# pcbgrado.net
KiCad netlist of a schematic drawn in Altium Designer
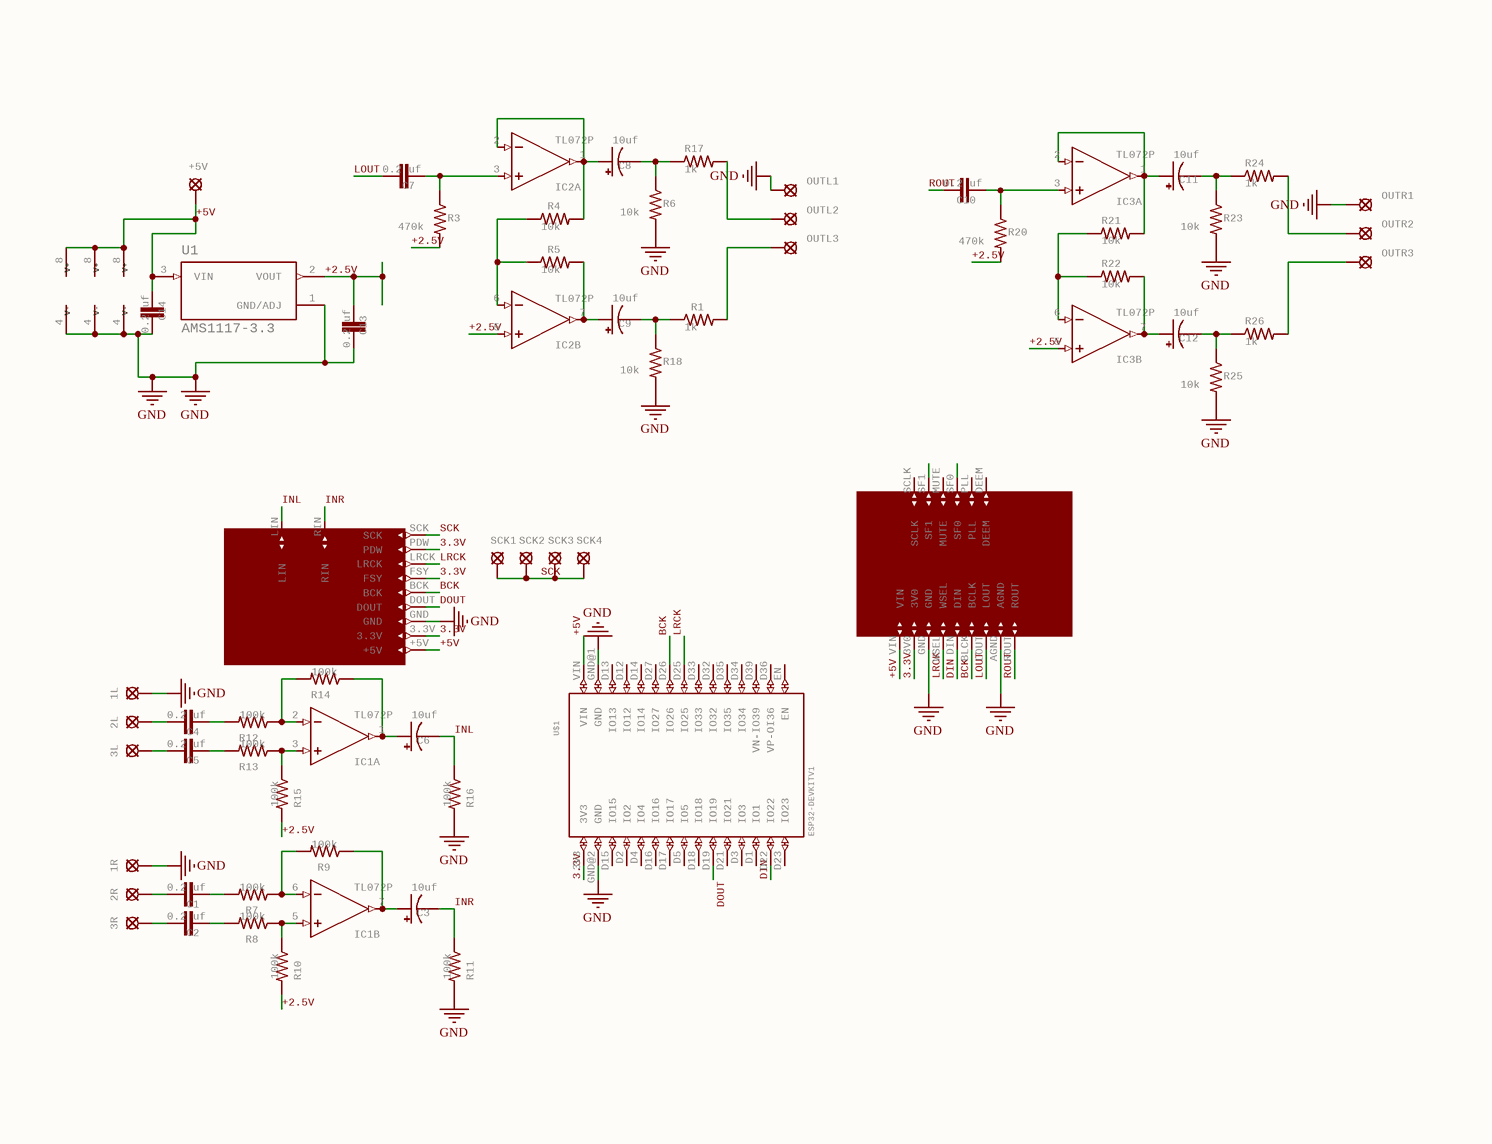
[diagram p0: pcbgrado.SchDoc]

(export (version "E")
  (design (tool "Eeschema 10.0.6"))
  (components
    (comp (ref "+5V")
      (value "LSP10")
      (footprint "LSP10")
      (description "SOLDER PAD    drill 1.0 mm, distributor Buerklin, 12H555")
      (fields (field (name "LIBRARYNAME") "solpad"))
      (libsource (lib "solpad") (part "LSP10"))
    )
    (comp (ref "1L")
      (value "LSP10")
      (footprint "LSP10")
      (description "SOLDER PAD    drill 1.0 mm, distributor Buerklin, 12H555")
      (fields (field (name "LIBRARYNAME") "solpad"))
      (libsource (lib "solpad") (part "LSP10"))
    )
    (comp (ref "1R")
      (value "LSP10")
      (footprint "LSP10")
      (description "SOLDER PAD    drill 1.0 mm, distributor Buerklin, 12H555")
      (fields (field (name "LIBRARYNAME") "solpad"))
      (libsource (lib "solpad") (part "LSP10"))
    )
    (comp (ref "2L")
      (value "LSP10")
      (footprint "LSP10")
      (description "SOLDER PAD    drill 1.0 mm, distributor Buerklin, 12H555")
      (fields (field (name "LIBRARYNAME") "solpad"))
      (libsource (lib "solpad") (part "LSP10"))
    )
    (comp (ref "2R")
      (value "LSP10")
      (footprint "LSP10")
      (description "SOLDER PAD    drill 1.0 mm, distributor Buerklin, 12H555")
      (fields (field (name "LIBRARYNAME") "solpad"))
      (libsource (lib "solpad") (part "LSP10"))
    )
    (comp (ref "3L")
      (value "LSP10")
      (footprint "LSP10")
      (description "SOLDER PAD    drill 1.0 mm, distributor Buerklin, 12H555")
      (fields (field (name "LIBRARYNAME") "solpad"))
      (libsource (lib "solpad") (part "LSP10"))
    )
    (comp (ref "3R")
      (value "LSP10")
      (footprint "LSP10")
      (description "SOLDER PAD    drill 1.0 mm, distributor Buerklin, 12H555")
      (fields (field (name "LIBRARYNAME") "solpad"))
      (libsource (lib "solpad") (part "LSP10"))
    )
    (comp (ref "C1")
      (value "C-EU025-025X050")
      (footprint "C025-025X050")
      (description "CAPACITOR, European symbol")
      (fields (field (name "POPULARITY") "0.2 uf"))
      (libsource (lib "rcl") (part "C-EU025-025X050"))
    )
    (comp (ref "C2")
      (value "C-EU025-025X050")
      (footprint "C025-025X050")
      (description "CAPACITOR, European symbol")
      (fields (field (name "POPULARITY") "0.2 uf"))
      (libsource (lib "rcl") (part "C-EU025-025X050"))
    )
    (comp (ref "C3")
      (value "CPOL-USE1.8-4")
      (footprint "E1,8-4")
      (description "POLARIZED CAPACITOR, American symbol")
      (fields (field (name "POPULARITY") "10uf"))
      (libsource (lib "rcl") (part "CPOL-USE1.8-4"))
    )
    (comp (ref "C4")
      (value "C-EU025-025X050")
      (footprint "C025-025X050")
      (description "CAPACITOR, European symbol")
      (fields (field (name "POPULARITY") "0.2 uf"))
      (libsource (lib "rcl") (part "C-EU025-025X050"))
    )
    (comp (ref "C5")
      (value "C-EU025-025X050")
      (footprint "C025-025X050")
      (description "CAPACITOR, European symbol")
      (fields (field (name "POPULARITY") "0.2 uf"))
      (libsource (lib "rcl") (part "C-EU025-025X050"))
    )
    (comp (ref "C6")
      (value "CPOL-USE1.8-4")
      (footprint "E1,8-4")
      (description "POLARIZED CAPACITOR, American symbol")
      (fields (field (name "POPULARITY") "10uf"))
      (libsource (lib "rcl") (part "CPOL-USE1.8-4"))
    )
    (comp (ref "C7")
      (value "C-EU025-030X050")
      (footprint "C025-030X050")
      (description "CAPACITOR, European symbol")
      (fields (field (name "POPULARITY") "0.2 uf"))
      (libsource (lib "rcl") (part "C-EU025-030X050"))
    )
    (comp (ref "C8")
      (value "CPOL-USE1.8-4")
      (footprint "E1,8-4")
      (description "POLARIZED CAPACITOR, American symbol")
      (fields (field (name "POPULARITY") "10uf"))
      (libsource (lib "rcl") (part "CPOL-USE1.8-4"))
    )
    (comp (ref "C9")
      (value "CPOL-USE1.8-4")
      (footprint "E1,8-4")
      (description "POLARIZED CAPACITOR, American symbol")
      (fields (field (name "POPULARITY") "10uf"))
      (libsource (lib "rcl") (part "CPOL-USE1.8-4"))
    )
    (comp (ref "C10")
      (value "C-EU025-030X050")
      (footprint "C025-030X050")
      (description "CAPACITOR, European symbol")
      (fields (field (name "POPULARITY") "0.2 uf"))
      (libsource (lib "rcl") (part "C-EU025-030X050"))
    )
    (comp (ref "C11")
      (value "CPOL-USE1.8-4")
      (footprint "E1,8-4")
      (description "POLARIZED CAPACITOR, American symbol")
      (fields (field (name "POPULARITY") "10uf"))
      (libsource (lib "rcl") (part "CPOL-USE1.8-4"))
    )
    (comp (ref "C12")
      (value "CPOL-USE1.8-4")
      (footprint "E1,8-4")
      (description "POLARIZED CAPACITOR, American symbol")
      (fields (field (name "POPULARITY") "10uf"))
      (libsource (lib "rcl") (part "CPOL-USE1.8-4"))
    )
    (comp (ref "C13")
      (value "C-EU025-025X050")
      (footprint "C025-025X050")
      (description "CAPACITOR, European symbol")
      (fields (field (name "POPULARITY") "0.2 uf"))
      (libsource (lib "") (part "C-EU025-025X050_1"))
    )
    (comp (ref "C14")
      (value "C-EU025-025X050")
      (footprint "C025-025X050")
      (description "CAPACITOR, European symbol")
      (fields (field (name "POPULARITY") "0.2 uf"))
      (libsource (lib "") (part "C-EU025-025X050_1"))
    )
    (comp (ref "IC1")
      (value "TL072P")
      (footprint "DIL08")
      (description "OP AMP")
      (fields (field (name "V+") "V+") (field (name "V-") "V-"))
      (libsource (lib "linear") (part "TL072P"))
    )
    (comp (ref "IC2")
      (value "TL072P")
      (footprint "DIL08")
      (description "OP AMP")
      (fields (field (name "V+") "V+") (field (name "V-") "V-"))
      (libsource (lib "linear") (part "TL072P"))
    )
    (comp (ref "IC3")
      (value "TL072P")
      (footprint "DIL08")
      (description "OP AMP")
      (fields (field (name "V+") "V+") (field (name "V-") "V-"))
      (libsource (lib "linear") (part "TL072P"))
    )
    (comp (ref "OUTL1")
      (value "LSP10")
      (footprint "LSP10")
      (description "SOLDER PAD    drill 1.0 mm, distributor Buerklin, 12H555")
      (fields (field (name "LIBRARYNAME") "solpad"))
      (libsource (lib "solpad") (part "LSP10"))
    )
    (comp (ref "OUTL2")
      (value "LSP10")
      (footprint "LSP10")
      (description "SOLDER PAD    drill 1.0 mm, distributor Buerklin, 12H555")
      (fields (field (name "LIBRARYNAME") "solpad"))
      (libsource (lib "solpad") (part "LSP10"))
    )
    (comp (ref "OUTL3")
      (value "LSP10")
      (footprint "LSP10")
      (description "SOLDER PAD    drill 1.0 mm, distributor Buerklin, 12H555")
      (fields (field (name "LIBRARYNAME") "solpad"))
      (libsource (lib "solpad") (part "LSP10"))
    )
    (comp (ref "OUTR1")
      (value "LSP10")
      (footprint "LSP10")
      (description "SOLDER PAD    drill 1.0 mm, distributor Buerklin, 12H555")
      (fields (field (name "LIBRARYNAME") "solpad"))
      (libsource (lib "solpad") (part "LSP10"))
    )
    (comp (ref "OUTR2")
      (value "LSP10")
      (footprint "LSP10")
      (description "SOLDER PAD    drill 1.0 mm, distributor Buerklin, 12H555")
      (fields (field (name "LIBRARYNAME") "solpad"))
      (libsource (lib "solpad") (part "LSP10"))
    )
    (comp (ref "OUTR3")
      (value "LSP10")
      (footprint "LSP10")
      (description "SOLDER PAD    drill 1.0 mm, distributor Buerklin, 12H555")
      (fields (field (name "LIBRARYNAME") "solpad"))
      (libsource (lib "solpad") (part "LSP10"))
    )
    (comp (ref "R1")
      (value "R-US_0204/7")
      (footprint "0204/7")
      (description "RESISTOR, American symbol")
      (fields (field (name "POPULARITY") "1k"))
      (libsource (lib "rcl") (part "R-US_0204/7"))
    )
    (comp (ref "R3")
      (value "R-US_0204/7")
      (footprint "0204/7")
      (description "RESISTOR, American symbol")
      (fields (field (name "POPULARITY") "470k"))
      (libsource (lib "rcl") (part "R-US_0204/7"))
    )
    (comp (ref "R4")
      (value "R-US_0204/7")
      (footprint "0204/7")
      (description "RESISTOR, American symbol")
      (fields (field (name "POPULARITY") "10k"))
      (libsource (lib "rcl") (part "R-US_0204/7"))
    )
    (comp (ref "R5")
      (value "R-US_0204/7")
      (footprint "0204/7")
      (description "RESISTOR, American symbol")
      (fields (field (name "POPULARITY") "10k"))
      (libsource (lib "rcl") (part "R-US_0204/7"))
    )
    (comp (ref "R6")
      (value "R-US_0204/7")
      (footprint "0204/7")
      (description "RESISTOR, American symbol")
      (fields (field (name "POPULARITY") "10k"))
      (libsource (lib "rcl") (part "R-US_0204/7"))
    )
    (comp (ref "R7")
      (value "R-US_0204/7")
      (footprint "0204/7")
      (description "RESISTOR, American symbol")
      (fields (field (name "POPULARITY") "100k"))
      (libsource (lib "rcl") (part "R-US_0204/7"))
    )
    (comp (ref "R8")
      (value "R-US_0204/7")
      (footprint "0204/7")
      (description "RESISTOR, American symbol")
      (fields (field (name "POPULARITY") "100k"))
      (libsource (lib "rcl") (part "R-US_0204/7"))
    )
    (comp (ref "R9")
      (value "R-US_0204/7")
      (footprint "0204/7")
      (description "RESISTOR, American symbol")
      (fields (field (name "POPULARITY") "100k"))
      (libsource (lib "rcl") (part "R-US_0204/7"))
    )
    (comp (ref "R10")
      (value "R-US_0204/7")
      (footprint "0204/7")
      (description "RESISTOR, American symbol")
      (fields (field (name "POPULARITY") "100k"))
      (libsource (lib "rcl") (part "R-US_0204/7"))
    )
    (comp (ref "R11")
      (value "R-US_0204/7")
      (footprint "0204/7")
      (description "RESISTOR, American symbol")
      (fields (field (name "POPULARITY") "100k"))
      (libsource (lib "rcl") (part "R-US_0204/7"))
    )
    (comp (ref "R12")
      (value "R-US_0204/7")
      (footprint "0204/7")
      (description "RESISTOR, American symbol")
      (fields (field (name "POPULARITY") "100k"))
      (libsource (lib "rcl") (part "R-US_0204/7"))
    )
    (comp (ref "R13")
      (value "R-US_0204/7")
      (footprint "0204/7")
      (description "RESISTOR, American symbol")
      (fields (field (name "POPULARITY") "100k"))
      (libsource (lib "rcl") (part "R-US_0204/7"))
    )
    (comp (ref "R14")
      (value "R-US_0204/7")
      (footprint "0204/7")
      (description "RESISTOR, American symbol")
      (fields (field (name "POPULARITY") "100k"))
      (libsource (lib "rcl") (part "R-US_0204/7"))
    )
    (comp (ref "R15")
      (value "R-US_0204/7")
      (footprint "0204/7")
      (description "RESISTOR, American symbol")
      (fields (field (name "POPULARITY") "100k"))
      (libsource (lib "rcl") (part "R-US_0204/7"))
    )
    (comp (ref "R16")
      (value "R-US_0204/7")
      (footprint "0204/7")
      (description "RESISTOR, American symbol")
      (fields (field (name "POPULARITY") "100k"))
      (libsource (lib "rcl") (part "R-US_0204/7"))
    )
    (comp (ref "R17")
      (value "R-US_0204/7")
      (footprint "0204/7")
      (description "RESISTOR, American symbol")
      (fields (field (name "POPULARITY") "1k"))
      (libsource (lib "rcl") (part "R-US_0204/7"))
    )
    (comp (ref "R18")
      (value "R-US_0204/7")
      (footprint "0204/7")
      (description "RESISTOR, American symbol")
      (fields (field (name "POPULARITY") "10k"))
      (libsource (lib "rcl") (part "R-US_0204/7"))
    )
    (comp (ref "R20")
      (value "R-US_0204/7")
      (footprint "0204/7")
      (description "RESISTOR, American symbol")
      (fields (field (name "POPULARITY") "470k"))
      (libsource (lib "rcl") (part "R-US_0204/7"))
    )
    (comp (ref "R21")
      (value "R-US_0204/7")
      (footprint "0204/7")
      (description "RESISTOR, American symbol")
      (fields (field (name "POPULARITY") "10k"))
      (libsource (lib "rcl") (part "R-US_0204/7"))
    )
    (comp (ref "R22")
      (value "R-US_0204/7")
      (footprint "0204/7")
      (description "RESISTOR, American symbol")
      (fields (field (name "POPULARITY") "10k"))
      (libsource (lib "rcl") (part "R-US_0204/7"))
    )
    (comp (ref "R23")
      (value "R-US_0204/7")
      (footprint "0204/7")
      (description "RESISTOR, American symbol")
      (fields (field (name "POPULARITY") "10k"))
      (libsource (lib "rcl") (part "R-US_0204/7"))
    )
    (comp (ref "R24")
      (value "R-US_0204/7")
      (footprint "0204/7")
      (description "RESISTOR, American symbol")
      (fields (field (name "POPULARITY") "1k"))
      (libsource (lib "rcl") (part "R-US_0204/7"))
    )
    (comp (ref "R25")
      (value "R-US_0204/7")
      (footprint "0204/7")
      (description "RESISTOR, American symbol")
      (fields (field (name "POPULARITY") "10k"))
      (libsource (lib "rcl") (part "R-US_0204/7"))
    )
    (comp (ref "R26")
      (value "R-US_0204/7")
      (footprint "0204/7")
      (description "RESISTOR, American symbol")
      (fields (field (name "POPULARITY") "1k"))
      (libsource (lib "rcl") (part "R-US_0204/7"))
    )
    (comp (ref "SCK1")
      (value "LSP10")
      (footprint "LSP10")
      (description "SOLDER PAD    drill 1.0 mm, distributor Buerklin, 12H555")
      (fields (field (name "LIBRARYNAME") "solpad"))
      (libsource (lib "solpad") (part "LSP10"))
    )
    (comp (ref "SCK2")
      (value "LSP10")
      (footprint "LSP10")
      (description "SOLDER PAD    drill 1.0 mm, distributor Buerklin, 12H555")
      (fields (field (name "LIBRARYNAME") "solpad"))
      (libsource (lib "solpad") (part "LSP10"))
    )
    (comp (ref "SCK3")
      (value "LSP10")
      (footprint "LSP10")
      (description "SOLDER PAD    drill 1.0 mm, distributor Buerklin, 12H555")
      (fields (field (name "LIBRARYNAME") "solpad"))
      (libsource (lib "solpad") (part "LSP10"))
    )
    (comp (ref "SCK4")
      (value "LSP10")
      (footprint "LSP10")
      (description "SOLDER PAD    drill 1.0 mm, distributor Buerklin, 12H555")
      (fields (field (name "LIBRARYNAME") "solpad"))
      (libsource (lib "solpad") (part "LSP10"))
    )
    (comp (ref "U$1")
      (value "ESP32DEVKITV1")
      (footprint "ESP32-DEVKITV1")
      (fields (field (name "ESP32-DEVKITV1") "ESP32-DEVKITV1"))
      (libsource (lib "ESP32-DEVKITV1") (part "ESP32DEVKITV1"))
    )
    (comp (ref "U$2")
      (value "PCM1802DIS")
      (footprint "PCM1802PC")
      (libsource (lib "PCM1802SIM") (part "PCM1802DIS"))
    )
    (comp (ref "U$3")
      (value "UDA1334A")
      (footprint "UDA1334A")
      (libsource (lib "uda1334a") (part "UDA1334A"))
    )
    (comp (ref "U1")
      (value "AMS1117-3.3")
      (footprint "SOT229P700X180-4N")
      (description "Check availability")
      (fields (field (name "MF") "Advanced Monolithic Systems"))
      (libsource (lib "AMS1117-3.3") (part "AMS1117-3.3"))
    )
  )
  (nets
    (net (code "1") (name "/+2.5V") (class "Default")
      (node (ref "C13") (pin "2") (pinfunction "2_2") (pintype "passive"))
      (node (ref "IC2") (pin "5") (pinfunction "+IN_5") (pintype "input"))
      (node (ref "IC3") (pin "5") (pinfunction "+IN_5") (pintype "input"))
      (node (ref "R10") (pin "2") (pinfunction "2_2") (pintype "passive"))
      (node (ref "R15") (pin "2") (pinfunction "2_2") (pintype "passive"))
      (node (ref "R20") (pin "2") (pinfunction "2_2") (pintype "passive"))
      (node (ref "R3") (pin "2") (pinfunction "2_2") (pintype "passive"))
      (node (ref "U1") (pin "2") (pinfunction "VOUT_2") (pintype "output"))
    )
    (net (code "2") (name "/+5V") (class "Default")
      (node (ref "+5V") (pin "MP") (pinfunction "MP_MP") (pintype "passive"))
      (node (ref "C14") (pin "2") (pinfunction "2_2") (pintype "passive"))
      (node (ref "IC1") (pin "8") (pinfunction "V+_8") (pintype "power_in"))
      (node (ref "IC2") (pin "8") (pinfunction "V+_8") (pintype "power_in"))
      (node (ref "IC3") (pin "8") (pinfunction "V+_8") (pintype "power_in"))
      (node (ref "U$1") (pin "VIN") (pinfunction "VIN_VIN") (pintype "bidirectional"))
      (node (ref "U$2") (pin "+5V") (pinfunction "+5V_+5V") (pintype "bidirectional"))
      (node (ref "U$3") (pin "VIN") (pinfunction "VIN_VIN") (pintype "bidirectional"))
      (node (ref "U1") (pin "3") (pinfunction "VIN_3") (pintype "input"))
    )
    (net (code "3") (name "/3.3V") (class "Default")
      (node (ref "U$1") (pin "3V3") (pinfunction "3V3_3V3") (pintype "bidirectional"))
      (node (ref "U$2") (pin "3.3V") (pinfunction "3.3V_3.3V") (pintype "bidirectional"))
      (node (ref "U$2") (pin "FSY") (pinfunction "FSY_FSY") (pintype "bidirectional"))
      (node (ref "U$2") (pin "PDW") (pinfunction "PDW_PDW") (pintype "bidirectional"))
      (node (ref "U$3") (pin "3V0") (pinfunction "3V0_3V0") (pintype "bidirectional"))
    )
    (net (code "4") (name "/BCK") (class "Default")
      (node (ref "U$1") (pin "D26") (pinfunction "IO26_D26") (pintype "bidirectional"))
      (node (ref "U$2") (pin "BCK") (pinfunction "BCK_BCK") (pintype "bidirectional"))
      (node (ref "U$3") (pin "BLCK") (pinfunction "BCLK_BLCK") (pintype "bidirectional"))
    )
    (net (code "5") (name "/DIN") (class "Default")
      (node (ref "U$1") (pin "D22") (pinfunction "IO22_D22") (pintype "bidirectional"))
      (node (ref "U$3") (pin "DIN") (pinfunction "DIN_DIN") (pintype "bidirectional"))
    )
    (net (code "6") (name "/DOUT") (class "Default")
      (node (ref "U$1") (pin "D19") (pinfunction "IO19_D19") (pintype "bidirectional"))
      (node (ref "U$2") (pin "DOUT") (pinfunction "DOUT_DOUT") (pintype "bidirectional"))
    )
    (net (code "7") (name "/INL") (class "Default")
      (node (ref "C6") (pin "-") (pinfunction "-_-") (pintype "passive"))
      (node (ref "R16") (pin "1") (pinfunction "1_1") (pintype "passive"))
      (node (ref "U$2") (pin "LIN") (pinfunction "LIN_LIN") (pintype "bidirectional"))
    )
    (net (code "8") (name "/INR") (class "Default")
      (node (ref "C3") (pin "-") (pinfunction "-_-") (pintype "passive"))
      (node (ref "R11") (pin "1") (pinfunction "1_1") (pintype "passive"))
      (node (ref "U$2") (pin "RIN") (pinfunction "RIN_RIN") (pintype "bidirectional"))
    )
    (net (code "9") (name "/LOUT") (class "Default")
      (node (ref "C7") (pin "1") (pinfunction "1_1") (pintype "passive"))
      (node (ref "U$3") (pin "LOUT") (pinfunction "LOUT_LOUT") (pintype "bidirectional"))
    )
    (net (code "10") (name "/LRCK") (class "Default")
      (node (ref "U$1") (pin "D25") (pinfunction "IO25_D25") (pintype "bidirectional"))
      (node (ref "U$2") (pin "LRCK") (pinfunction "LRCK_LRCK") (pintype "bidirectional"))
      (node (ref "U$3") (pin "WSEL") (pinfunction "WSEL_WSEL") (pintype "bidirectional"))
    )
    (net (code "11") (name "/ROUT") (class "Default")
      (node (ref "C10") (pin "1") (pinfunction "1_1") (pintype "passive"))
      (node (ref "U$3") (pin "ROUT") (pinfunction "ROUT_ROUT") (pintype "bidirectional"))
    )
    (net (code "12") (name "/SCK") (class "Default")
      (node (ref "SCK1") (pin "MP") (pinfunction "MP_MP") (pintype "passive"))
      (node (ref "SCK2") (pin "MP") (pinfunction "MP_MP") (pintype "passive"))
      (node (ref "SCK3") (pin "MP") (pinfunction "MP_MP") (pintype "passive"))
      (node (ref "SCK4") (pin "MP") (pinfunction "MP_MP") (pintype "passive"))
      (node (ref "U$2") (pin "SCK") (pinfunction "SCK_SCK") (pintype "bidirectional"))
    )
    (net (code "13") (name "GND") (class "Default")
      (node (ref "1L") (pin "MP") (pinfunction "MP_MP") (pintype "passive"))
      (node (ref "1R") (pin "MP") (pinfunction "MP_MP") (pintype "passive"))
      (node (ref "C13") (pin "1") (pinfunction "1_1") (pintype "passive"))
      (node (ref "C14") (pin "1") (pinfunction "1_1") (pintype "passive"))
      (node (ref "IC1") (pin "4") (pinfunction "V-_4") (pintype "power_in"))
      (node (ref "IC2") (pin "4") (pinfunction "V-_4") (pintype "power_in"))
      (node (ref "IC3") (pin "4") (pinfunction "V-_4") (pintype "power_in"))
      (node (ref "OUTL1") (pin "MP") (pinfunction "MP_MP") (pintype "passive"))
      (node (ref "OUTR1") (pin "MP") (pinfunction "MP_MP") (pintype "passive"))
      (node (ref "R11") (pin "2") (pinfunction "2_2") (pintype "passive"))
      (node (ref "R16") (pin "2") (pinfunction "2_2") (pintype "passive"))
      (node (ref "R18") (pin "2") (pinfunction "2_2") (pintype "passive"))
      (node (ref "R23") (pin "2") (pinfunction "2_2") (pintype "passive"))
      (node (ref "R25") (pin "2") (pinfunction "2_2") (pintype "passive"))
      (node (ref "R6") (pin "2") (pinfunction "2_2") (pintype "passive"))
      (node (ref "U$1") (pin "GND@1") (pinfunction "GND_GND@1") (pintype "bidirectional"))
      (node (ref "U$1") (pin "GND@2") (pinfunction "GND_GND@2") (pintype "bidirectional"))
      (node (ref "U$2") (pin "GND") (pinfunction "GND_GND") (pintype "bidirectional"))
      (node (ref "U$3") (pin "AGND") (pinfunction "AGND_AGND") (pintype "bidirectional"))
      (node (ref "U$3") (pin "GND") (pinfunction "GND_GND") (pintype "bidirectional"))
      (node (ref "U1") (pin "1") (pinfunction "GND/ADJ_1") (pintype "power_in"))
    )
    (net (code "14") (name "Net-(2L-PadMP)") (class "Default")
      (node (ref "2L") (pin "MP") (pinfunction "MP_MP") (pintype "passive"))
      (node (ref "C4") (pin "1") (pinfunction "1_1") (pintype "passive"))
    )
    (net (code "15") (name "Net-(2R-PadMP)") (class "Default")
      (node (ref "2R") (pin "MP") (pinfunction "MP_MP") (pintype "passive"))
      (node (ref "C1") (pin "1") (pinfunction "1_1") (pintype "passive"))
    )
    (net (code "16") (name "Net-(3L-PadMP)") (class "Default")
      (node (ref "3L") (pin "MP") (pinfunction "MP_MP") (pintype "passive"))
      (node (ref "C5") (pin "1") (pinfunction "1_1") (pintype "passive"))
    )
    (net (code "17") (name "Net-(3R-PadMP)") (class "Default")
      (node (ref "3R") (pin "MP") (pinfunction "MP_MP") (pintype "passive"))
      (node (ref "C2") (pin "1") (pinfunction "1_1") (pintype "passive"))
    )
    (net (code "18") (name "Net-(C1-Pad2)") (class "Default")
      (node (ref "C1") (pin "2") (pinfunction "2_2") (pintype "passive"))
      (node (ref "R7") (pin "2") (pinfunction "2_2") (pintype "passive"))
    )
    (net (code "19") (name "Net-(C2-Pad2)") (class "Default")
      (node (ref "C2") (pin "2") (pinfunction "2_2") (pintype "passive"))
      (node (ref "R8") (pin "2") (pinfunction "2_2") (pintype "passive"))
    )
    (net (code "20") (name "Net-(C4-Pad2)") (class "Default")
      (node (ref "C4") (pin "2") (pinfunction "2_2") (pintype "passive"))
      (node (ref "R12") (pin "2") (pinfunction "2_2") (pintype "passive"))
    )
    (net (code "21") (name "Net-(C5-Pad2)") (class "Default")
      (node (ref "C5") (pin "2") (pinfunction "2_2") (pintype "passive"))
      (node (ref "R13") (pin "2") (pinfunction "2_2") (pintype "passive"))
    )
    (net (code "22") (name "Net-(C8-Pad-)") (class "Default")
      (node (ref "C8") (pin "-") (pinfunction "-_-") (pintype "passive"))
      (node (ref "R17") (pin "1") (pinfunction "1_1") (pintype "passive"))
      (node (ref "R6") (pin "1") (pinfunction "1_1") (pintype "passive"))
    )
    (net (code "23") (name "Net-(C9-Pad-)") (class "Default")
      (node (ref "C9") (pin "-") (pinfunction "-_-") (pintype "passive"))
      (node (ref "R1") (pin "1") (pinfunction "1_1") (pintype "passive"))
      (node (ref "R18") (pin "1") (pinfunction "1_1") (pintype "passive"))
    )
    (net (code "24") (name "Net-(C11-Pad-)") (class "Default")
      (node (ref "C11") (pin "-") (pinfunction "-_-") (pintype "passive"))
      (node (ref "R23") (pin "1") (pinfunction "1_1") (pintype "passive"))
      (node (ref "R24") (pin "1") (pinfunction "1_1") (pintype "passive"))
    )
    (net (code "25") (name "Net-(C12-Pad-)") (class "Default")
      (node (ref "C12") (pin "-") (pinfunction "-_-") (pintype "passive"))
      (node (ref "R25") (pin "1") (pinfunction "1_1") (pintype "passive"))
      (node (ref "R26") (pin "1") (pinfunction "1_1") (pintype "passive"))
    )
    (net (code "26") (name "Net-(IC1A-+IN)") (class "Default")
      (node (ref "IC1") (pin "3") (pinfunction "+IN_3") (pintype "input"))
      (node (ref "R13") (pin "1") (pinfunction "1_1") (pintype "passive"))
      (node (ref "R15") (pin "1") (pinfunction "1_1") (pintype "passive"))
    )
    (net (code "27") (name "Net-(IC1A--IN)") (class "Default")
      (node (ref "IC1") (pin "2") (pinfunction "-IN_2") (pintype "input"))
      (node (ref "R12") (pin "1") (pinfunction "1_1") (pintype "passive"))
      (node (ref "R14") (pin "2") (pinfunction "2_2") (pintype "passive"))
    )
    (net (code "28") (name "Net-(IC1A-OUT)") (class "Default")
      (node (ref "C6") (pin "+") (pinfunction "+_+") (pintype "passive"))
      (node (ref "IC1") (pin "1") (pinfunction "OUT_1") (pintype "output"))
      (node (ref "R14") (pin "1") (pinfunction "1_1") (pintype "passive"))
    )
    (net (code "29") (name "Net-(IC1B-+IN)") (class "Default")
      (node (ref "IC1") (pin "5") (pinfunction "+IN_5") (pintype "input"))
      (node (ref "R10") (pin "1") (pinfunction "1_1") (pintype "passive"))
      (node (ref "R8") (pin "1") (pinfunction "1_1") (pintype "passive"))
    )
    (net (code "30") (name "Net-(IC1B--IN)") (class "Default")
      (node (ref "IC1") (pin "6") (pinfunction "-IN_6") (pintype "input"))
      (node (ref "R7") (pin "1") (pinfunction "1_1") (pintype "passive"))
      (node (ref "R9") (pin "2") (pinfunction "2_2") (pintype "passive"))
    )
    (net (code "31") (name "Net-(IC1B-OUT)") (class "Default")
      (node (ref "C3") (pin "+") (pinfunction "+_+") (pintype "passive"))
      (node (ref "IC1") (pin "7") (pinfunction "OUT_7") (pintype "output"))
      (node (ref "R9") (pin "1") (pinfunction "1_1") (pintype "passive"))
    )
    (net (code "32") (name "Net-(IC2A-+IN)") (class "Default")
      (node (ref "C7") (pin "2") (pinfunction "2_2") (pintype "passive"))
      (node (ref "IC2") (pin "3") (pinfunction "+IN_3") (pintype "input"))
      (node (ref "R3") (pin "1") (pinfunction "1_1") (pintype "passive"))
    )
    (net (code "33") (name "Net-(IC2A--IN)") (class "Default")
      (node (ref "C8") (pin "+") (pinfunction "+_+") (pintype "passive"))
      (node (ref "IC2") (pin "1") (pinfunction "OUT_1") (pintype "output"))
      (node (ref "IC2") (pin "2") (pinfunction "-IN_2") (pintype "input"))
      (node (ref "R4") (pin "2") (pinfunction "2_2") (pintype "passive"))
    )
    (net (code "34") (name "Net-(IC2B--IN)") (class "Default")
      (node (ref "IC2") (pin "6") (pinfunction "-IN_6") (pintype "input"))
      (node (ref "R4") (pin "1") (pinfunction "1_1") (pintype "passive"))
      (node (ref "R5") (pin "1") (pinfunction "1_1") (pintype "passive"))
    )
    (net (code "35") (name "Net-(IC2B-OUT)") (class "Default")
      (node (ref "C9") (pin "+") (pinfunction "+_+") (pintype "passive"))
      (node (ref "IC2") (pin "7") (pinfunction "OUT_7") (pintype "output"))
      (node (ref "R5") (pin "2") (pinfunction "2_2") (pintype "passive"))
    )
    (net (code "36") (name "Net-(IC3A-+IN)") (class "Default")
      (node (ref "C10") (pin "2") (pinfunction "2_2") (pintype "passive"))
      (node (ref "IC3") (pin "3") (pinfunction "+IN_3") (pintype "input"))
      (node (ref "R20") (pin "1") (pinfunction "1_1") (pintype "passive"))
    )
    (net (code "37") (name "Net-(IC3A--IN)") (class "Default")
      (node (ref "C11") (pin "+") (pinfunction "+_+") (pintype "passive"))
      (node (ref "IC3") (pin "1") (pinfunction "OUT_1") (pintype "output"))
      (node (ref "IC3") (pin "2") (pinfunction "-IN_2") (pintype "input"))
      (node (ref "R21") (pin "2") (pinfunction "2_2") (pintype "passive"))
    )
    (net (code "38") (name "Net-(IC3B--IN)") (class "Default")
      (node (ref "IC3") (pin "6") (pinfunction "-IN_6") (pintype "input"))
      (node (ref "R21") (pin "1") (pinfunction "1_1") (pintype "passive"))
      (node (ref "R22") (pin "1") (pinfunction "1_1") (pintype "passive"))
    )
    (net (code "39") (name "Net-(IC3B-OUT)") (class "Default")
      (node (ref "C12") (pin "+") (pinfunction "+_+") (pintype "passive"))
      (node (ref "IC3") (pin "7") (pinfunction "OUT_7") (pintype "output"))
      (node (ref "R22") (pin "2") (pinfunction "2_2") (pintype "passive"))
    )
    (net (code "40") (name "Net-(OUTL2-PadMP)") (class "Default")
      (node (ref "OUTL2") (pin "MP") (pinfunction "MP_MP") (pintype "passive"))
      (node (ref "R17") (pin "2") (pinfunction "2_2") (pintype "passive"))
    )
    (net (code "41") (name "Net-(OUTL3-PadMP)") (class "Default")
      (node (ref "OUTL3") (pin "MP") (pinfunction "MP_MP") (pintype "passive"))
      (node (ref "R1") (pin "2") (pinfunction "2_2") (pintype "passive"))
    )
    (net (code "42") (name "Net-(OUTR2-PadMP)") (class "Default")
      (node (ref "OUTR2") (pin "MP") (pinfunction "MP_MP") (pintype "passive"))
      (node (ref "R24") (pin "2") (pinfunction "2_2") (pintype "passive"))
    )
    (net (code "43") (name "Net-(OUTR3-PadMP)") (class "Default")
      (node (ref "OUTR3") (pin "MP") (pinfunction "MP_MP") (pintype "passive"))
      (node (ref "R26") (pin "2") (pinfunction "2_2") (pintype "passive"))
    )
    (net (code "44") (name "unconnected-(U$1-IO1-PadD1)") (class "Default")
      (node (ref "U$1") (pin "D1") (pinfunction "IO1_D1") (pintype "bidirectional"))
    )
    (net (code "45") (name "unconnected-(U$1-IO2-PadD2)") (class "Default")
      (node (ref "U$1") (pin "D2") (pinfunction "IO2_D2") (pintype "bidirectional"))
    )
    (net (code "46") (name "unconnected-(U$1-IO3-PadD3)") (class "Default")
      (node (ref "U$1") (pin "D3") (pinfunction "IO3_D3") (pintype "bidirectional"))
    )
    (net (code "47") (name "unconnected-(U$1-IO4-PadD4)") (class "Default")
      (node (ref "U$1") (pin "D4") (pinfunction "IO4_D4") (pintype "bidirectional"))
    )
    (net (code "48") (name "unconnected-(U$1-IO5-PadD5)") (class "Default")
      (node (ref "U$1") (pin "D5") (pinfunction "IO5_D5") (pintype "bidirectional"))
    )
    (net (code "49") (name "unconnected-(U$1-IO12-PadD12)") (class "Default")
      (node (ref "U$1") (pin "D12") (pinfunction "IO12_D12") (pintype "bidirectional"))
    )
    (net (code "50") (name "unconnected-(U$1-IO13-PadD13)") (class "Default")
      (node (ref "U$1") (pin "D13") (pinfunction "IO13_D13") (pintype "bidirectional"))
    )
    (net (code "51") (name "unconnected-(U$1-IO14-PadD14)") (class "Default")
      (node (ref "U$1") (pin "D14") (pinfunction "IO14_D14") (pintype "bidirectional"))
    )
    (net (code "52") (name "unconnected-(U$1-IO15-PadD15)") (class "Default")
      (node (ref "U$1") (pin "D15") (pinfunction "IO15_D15") (pintype "bidirectional"))
    )
    (net (code "53") (name "unconnected-(U$1-IO16-PadD16)") (class "Default")
      (node (ref "U$1") (pin "D16") (pinfunction "IO16_D16") (pintype "bidirectional"))
    )
    (net (code "54") (name "unconnected-(U$1-IO17-PadD17)") (class "Default")
      (node (ref "U$1") (pin "D17") (pinfunction "IO17_D17") (pintype "bidirectional"))
    )
    (net (code "55") (name "unconnected-(U$1-IO18-PadD18)") (class "Default")
      (node (ref "U$1") (pin "D18") (pinfunction "IO18_D18") (pintype "bidirectional"))
    )
    (net (code "56") (name "unconnected-(U$1-IO21-PadD21)") (class "Default")
      (node (ref "U$1") (pin "D21") (pinfunction "IO21_D21") (pintype "bidirectional"))
    )
    (net (code "57") (name "unconnected-(U$1-IO23-PadD23)") (class "Default")
      (node (ref "U$1") (pin "D23") (pinfunction "IO23_D23") (pintype "bidirectional"))
    )
    (net (code "58") (name "unconnected-(U$1-IO27-PadD27)") (class "Default")
      (node (ref "U$1") (pin "D27") (pinfunction "IO27_D27") (pintype "bidirectional"))
    )
    (net (code "59") (name "unconnected-(U$1-IO32-PadD32)") (class "Default")
      (node (ref "U$1") (pin "D32") (pinfunction "IO32_D32") (pintype "bidirectional"))
    )
    (net (code "60") (name "unconnected-(U$1-IO33-PadD33)") (class "Default")
      (node (ref "U$1") (pin "D33") (pinfunction "IO33_D33") (pintype "bidirectional"))
    )
    (net (code "61") (name "unconnected-(U$1-IO34-PadD34)") (class "Default")
      (node (ref "U$1") (pin "D34") (pinfunction "IO34_D34") (pintype "bidirectional"))
    )
    (net (code "62") (name "unconnected-(U$1-IO35-PadD35)") (class "Default")
      (node (ref "U$1") (pin "D35") (pinfunction "IO35_D35") (pintype "bidirectional"))
    )
    (net (code "63") (name "unconnected-(U$1-PadEN)") (class "Default")
      (node (ref "U$1") (pin "EN") (pinfunction "EN_EN") (pintype "bidirectional"))
    )
    (net (code "64") (name "unconnected-(U$1-VN-IO39-PadD39)") (class "Default")
      (node (ref "U$1") (pin "D39") (pinfunction "VN-IO39_D39") (pintype "bidirectional"))
    )
    (net (code "65") (name "unconnected-(U$1-VP-OI36-PadD36)") (class "Default")
      (node (ref "U$1") (pin "D36") (pinfunction "VP-OI36_D36") (pintype "bidirectional"))
    )
    (net (code "66") (name "unconnected-(U$3-PadDEEM)") (class "Default")
      (node (ref "U$3") (pin "DEEM") (pinfunction "DEEM_DEEM") (pintype "bidirectional"))
    )
    (net (code "67") (name "unconnected-(U$3-PadMUTE)") (class "Default")
      (node (ref "U$3") (pin "MUTE") (pinfunction "MUTE_MUTE") (pintype "bidirectional"))
    )
    (net (code "68") (name "unconnected-(U$3-PadPLL)") (class "Default")
      (node (ref "U$3") (pin "PLL") (pinfunction "PLL_PLL") (pintype "bidirectional"))
    )
    (net (code "69") (name "unconnected-(U$3-PadSCLK)") (class "Default")
      (node (ref "U$3") (pin "SCLK") (pinfunction "SCLK_SCLK") (pintype "bidirectional"))
    )
    (net (code "70") (name "unconnected-(U$3-PadSF0)") (class "Default")
      (node (ref "U$3") (pin "SF0") (pinfunction "SF0_SF0") (pintype "bidirectional"))
    )
    (net (code "71") (name "unconnected-(U$3-PadSF1)") (class "Default")
      (node (ref "U$3") (pin "SF1") (pinfunction "SF1_SF1") (pintype "bidirectional"))
    )
  )
)
